# Sheet.net
KiCad netlist of a schematic drawn in Altium Designer
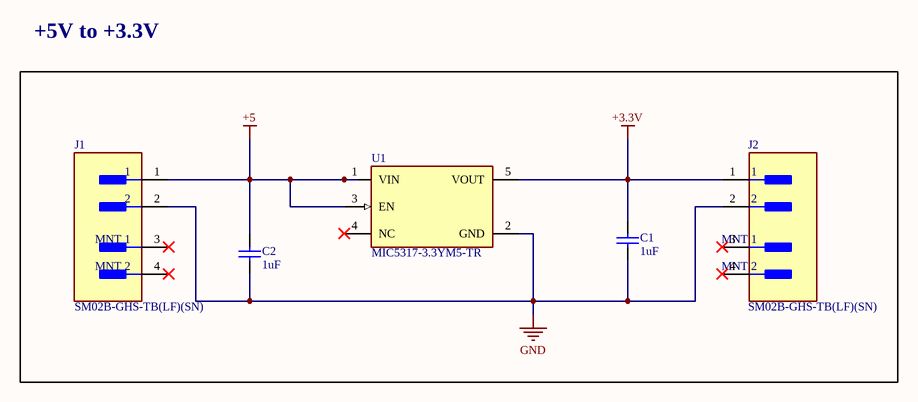
[diagram p0: Sheet.SchDoc]

(export (version "E")
  (design (tool "Eeschema 10.0.6"))
  (components
    (comp (ref "C1")
      (value "1uF")
      (footprint "CAPC2013X145X50NL20T20")
      (fields (field (name "PART NUMBER") "VJ0805Y105KXQRW1BC") (field (name "MANUFACTURER") "Vitramon"))
      (libsource (lib "Altium Content Vault") (part "CAP"))
    )
    (comp (ref "C2")
      (value "1uF")
      (footprint "CAPC2013X145X50NL20T20")
      (fields (field (name "PART NUMBER") "VJ0805Y105KXQRW1BC") (field (name "MANUFACTURER") "Vitramon"))
      (libsource (lib "Altium Content Vault") (part "CAP"))
    )
    (comp (ref "J1")
      (value "SM02B-GHS-TB(LF)(SN)")
      (footprint "FP-SM02B-GHS-TB_LF_SN-MFG")
      (description "CONN HEADER SMD R/A 2POS 1.25MM")
      (libsource (lib "Altium Content Vault") (part "56ec3178a87b3978bdc1b3682cd516a"))
    )
    (comp (ref "J2")
      (value "SM02B-GHS-TB(LF)(SN)")
      (footprint "FP-SM02B-GHS-TB_LF_SN-MFG")
      (description "CONN HEADER SMD R/A 2POS 1.25MM")
      (libsource (lib "") (part "56ec3178a87b3978bdc1b3682cd516a_1"))
    )
    (comp (ref "U1")
      (value "MIC5317-3.3YM5-TR")
      (footprint "FP-SOT23-5LD-PL-1-MFG")
      (description "IC REG LINEAR 3.3V 150MA SOT23-5")
      (libsource (lib "Altium Content Vault") (part "0a093dae7315cdc977fd108dde87457"))
    )
  )
  (nets
    (net (code "1") (name "+3.3V") (class "Default")
      (node (ref "C1") (pin "2") (pinfunction "2_2") (pintype "passive"))
      (node (ref "J2") (pin "1") (pinfunction "1_1") (pintype "passive"))
      (node (ref "U1") (pin "5") (pinfunction "VOUT_5") (pintype "power_in"))
    )
    (net (code "2") (name "+5") (class "Default")
      (node (ref "C2") (pin "2") (pinfunction "2_2") (pintype "passive"))
      (node (ref "J1") (pin "1") (pinfunction "1_1") (pintype "passive"))
      (node (ref "U1") (pin "1") (pinfunction "VIN_1") (pintype "power_in"))
      (node (ref "U1") (pin "3") (pinfunction "EN_3") (pintype "input"))
    )
    (net (code "3") (name "GND") (class "Default")
      (node (ref "C1") (pin "1") (pinfunction "1_1") (pintype "passive"))
      (node (ref "C2") (pin "1") (pinfunction "1_1") (pintype "passive"))
      (node (ref "J1") (pin "2") (pinfunction "2_2") (pintype "passive"))
      (node (ref "J2") (pin "2") (pinfunction "2_2") (pintype "passive"))
      (node (ref "U1") (pin "2") (pinfunction "GND_2") (pintype "power_in"))
    )
    (net (code "4") (name "unconnected-(J1-MNT_1-Pad3)") (class "Default")
      (node (ref "J1") (pin "3") (pinfunction "MNT_1_3") (pintype "passive+no_connect"))
    )
    (net (code "5") (name "unconnected-(J1-MNT_2-Pad4)") (class "Default")
      (node (ref "J1") (pin "4") (pinfunction "MNT_2_4") (pintype "passive+no_connect"))
    )
    (net (code "6") (name "unconnected-(J2-MNT_1-Pad3)") (class "Default")
      (node (ref "J2") (pin "3") (pinfunction "MNT_1_3") (pintype "passive+no_connect"))
    )
    (net (code "7") (name "unconnected-(J2-MNT_2-Pad4)") (class "Default")
      (node (ref "J2") (pin "4") (pinfunction "MNT_2_4") (pintype "passive+no_connect"))
    )
    (net (code "8") (name "unconnected-(U1-NC-Pad4)") (class "Default")
      (node (ref "U1") (pin "4") (pinfunction "NC_4") (pintype "passive+no_connect"))
    )
  )
)
